# Measurement.net
KiCad netlist of a schematic drawn in Altium Designer
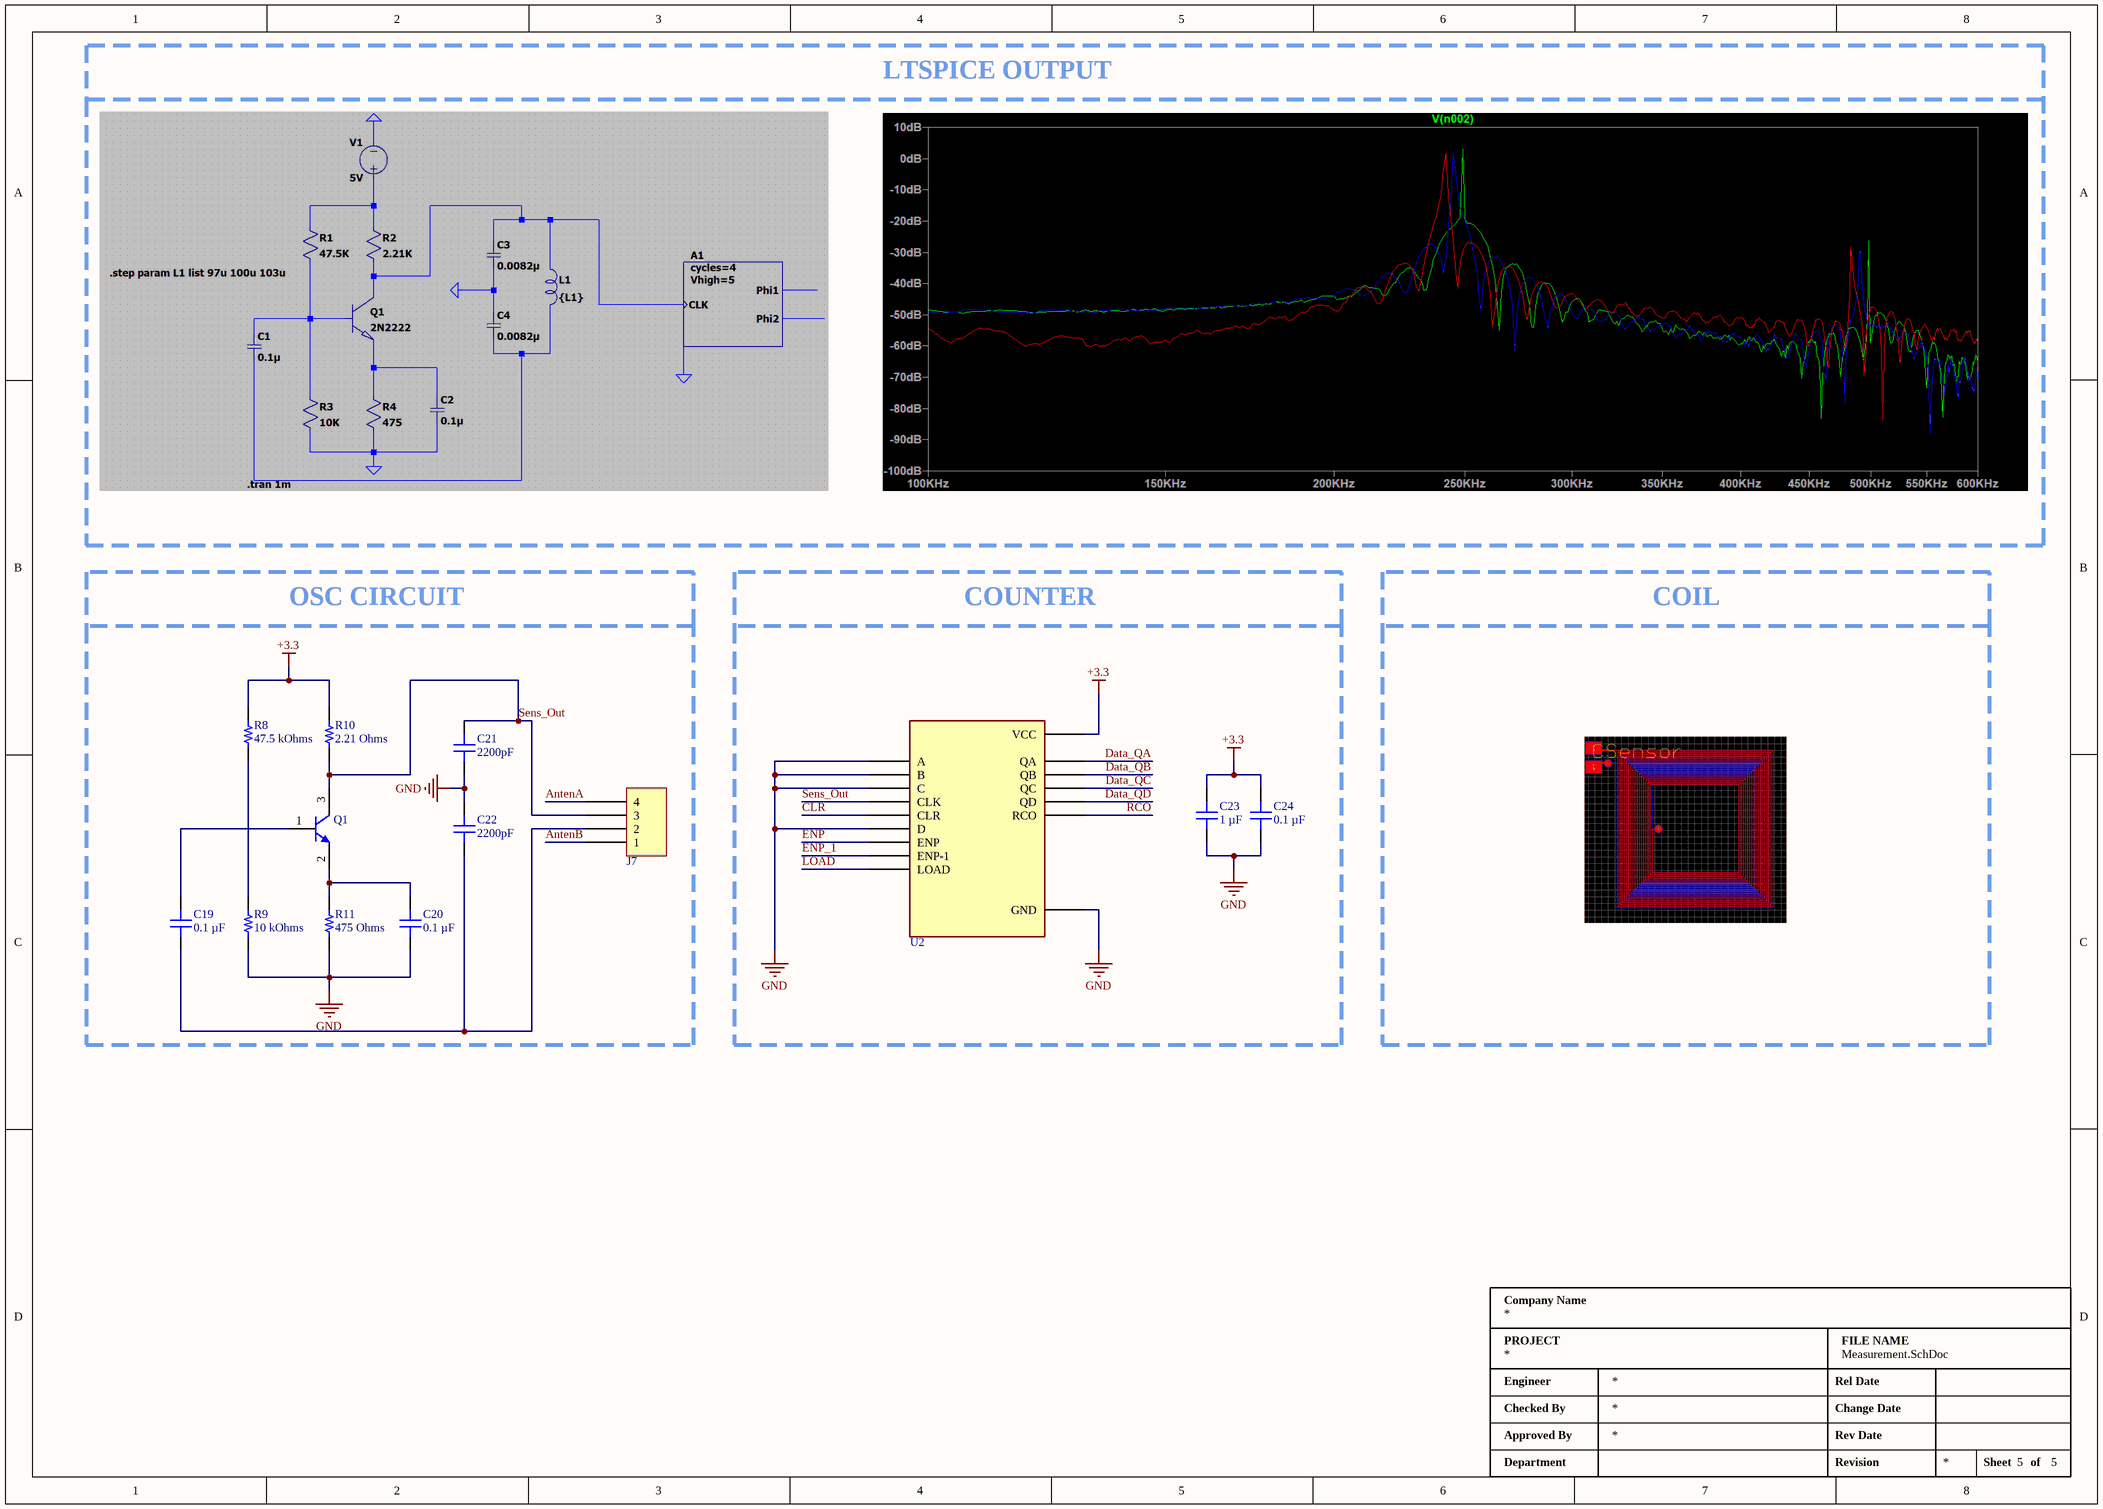
[diagram p0: Measurement.SchDoc]

(export (version "E")
  (design (tool "Eeschema 10.0.6"))
  (components
    (comp (ref "C19")
      (value "0.1 µF")
      (footprint "CAP 0603_1608")
      (description "CAP, Y5V, 0603, 0.1UF, +80/-20%,")
      (fields
        (field (name "PART NUMBER") "CML0603Y5V104ZT50V")
        (field (name "CAPACITANCE") "0.1 µF")
        (field (name "MANUFACTURER") "Stackpole Electronics Inc")
      )
      (libsource (lib "Celestial Altium Library - altium_library") (part "Capacitor"))
    )
    (comp (ref "C20")
      (value "0.1 µF")
      (footprint "CAP 0603_1608")
      (description "CAP, Y5V, 0603, 0.1UF, +80/-20%,")
      (fields
        (field (name "PART NUMBER") "CML0603Y5V104ZT50V")
        (field (name "CAPACITANCE") "0.1 µF")
        (field (name "MANUFACTURER") "Stackpole Electronics Inc")
      )
      (libsource (lib "Celestial Altium Library - altium_library") (part "Capacitor"))
    )
    (comp (ref "C21")
      (value "2200pF")
      (footprint "CAP 0603_1608")
      (description "CAP CER 2200PF 100V X7R 0603")
      (fields
        (field (name "PART NUMBER") "06031C222KAT4A")
        (field (name "CAPACITANCE") "2200pF")
        (field (name "MANUFACTURER") "AVX Corporation")
      )
      (libsource (lib "Celestial Altium Library - altium_library") (part "Capacitor"))
    )
    (comp (ref "C22")
      (value "2200pF")
      (footprint "CAP 0603_1608")
      (description "CAP CER 2200PF 100V X7R 0603")
      (fields
        (field (name "PART NUMBER") "06031C222KAT4A")
        (field (name "CAPACITANCE") "2200pF")
        (field (name "MANUFACTURER") "AVX Corporation")
      )
      (libsource (lib "Celestial Altium Library - altium_library") (part "Capacitor"))
    )
    (comp (ref "C23")
      (value "1 µF")
      (footprint "CAP 0603_1608")
      (description "CAP CER 0603 1UF 16V X7R 20%")
      (fields
        (field (name "PART NUMBER") "C0603X105M4RAC7867")
        (field (name "CAPACITANCE") "1 µF")
        (field (name "MANUFACTURER") "KEMET")
      )
      (libsource (lib "Celestial Altium Library - altium_library") (part "Capacitor"))
    )
    (comp (ref "C24")
      (value "0.1 µF")
      (footprint "CAP 0805_2012")
      (description "CAP CER 0805 0.1UF 100V X7R 5%")
      (fields
        (field (name "PART NUMBER") "C0805C104J1RECAUTO")
        (field (name "CAPACITANCE") "0.1 µF")
        (field (name "MANUFACTURER") "KEMET")
      )
      (libsource (lib "Celestial Altium Library - altium_library") (part "Capacitor"))
    )
    (comp (ref "J7")
      (value "SSW-104-03-T-S")
      (footprint "SAMTEC SSW-104-03-T-S")
      (description "CONN RCPT 4POS 0.1 TIN PCB")
      (fields (field (name "MANUFACTURER") "Samtec Inc."))
      (libsource (lib "Celestial Altium Library - altium_library") (part "4 Pin"))
    )
    (comp (ref "Q1")
      (value "MMBT489LT1G")
      (footprint "ON SEMI SOT-23-3")
      (description "TRANS NPN 30V 1A SOT23")
      (fields (field (name "MANUFACTURER") "ON Semiconductor"))
      (libsource (lib "Celestial Altium Library - altium_library") (part "ON SEMI NPN SOT-23-3"))
    )
    (comp (ref "R8")
      (value "47.5 kOhms")
      (footprint "RES 0603_1608")
      (description "RES SMD 47.5K OHM 0.1% 1/5W 0603")
      (fields
        (field (name "PART NUMBER") "ERJ-PB3B4752V")
        (field (name "MANUFACTURER") "Panasonic Electronic Components")
      )
      (libsource (lib "Celestial Altium Library - altium_library") (part "Resistor"))
    )
    (comp (ref "R9")
      (value "10 kOhms")
      (footprint "RES 0603_1608")
      (description "RES 10K OHM 0.1% 1/16W 0603")
      (fields
        (field (name "PART NUMBER") "RNCS0603BKE10K0")
        (field (name "MANUFACTURER") "Stackpole Electronics Inc")
      )
      (libsource (lib "Celestial Altium Library - altium_library") (part "Resistor"))
    )
    (comp (ref "R10")
      (value "2.21 Ohms")
      (footprint "RES 0603_1608")
      (description "CPF 0603 2R21 0.1% 25PPM 1K RL")
      (fields
        (field (name "PART NUMBER") "CPF0603B2R21E1")
        (field (name "MANUFACTURER") "TE Connectivity Passive Product")
      )
      (libsource (lib "Celestial Altium Library - altium_library") (part "Resistor"))
    )
    (comp (ref "R11")
      (value "475 Ohms")
      (footprint "RES 0603_1608")
      (description "RES SMD 475 OHM 0.5% 1/5W 0603")
      (fields
        (field (name "PART NUMBER") "ERJ-PB3D4750V")
        (field (name "MANUFACTURER") "Panasonic Electronic Components")
      )
      (libsource (lib "Celestial Altium Library - altium_library") (part "Resistor"))
    )
    (comp (ref "U2")
      (value "IC COUNTER 4BIT SYNC BIN 16-SOIC")
      (footprint "SOIC16")
      (fields
        (field (name "MANUFACTURER") "Texas Instruments")
        (field (name "MANUFACTURER PART NUMBER") "SN74HC163DR")
      )
      (libsource (lib "DcDcBuck") (part "SN74HC163D"))
    )
  )
  (nets
    (net (code "1") (name "+3.3") (class "Default")
      (node (ref "C23") (pin "2") (pinfunction "2_2") (pintype "passive"))
      (node (ref "C24") (pin "2") (pinfunction "2_2") (pintype "passive"))
      (node (ref "R10") (pin "2") (pinfunction "2_2") (pintype "passive"))
      (node (ref "R8") (pin "2") (pinfunction "2_2") (pintype "passive"))
      (node (ref "U2") (pin "16") (pinfunction "VCC_16") (pintype "passive"))
    )
    (net (code "2") (name "/AntenA") (class "Default")
      (node (ref "J7") (pin "4") (pinfunction "4_4") (pintype "passive"))
    )
    (net (code "3") (name "/AntenB") (class "Default")
      (node (ref "J7") (pin "1") (pinfunction "1_1") (pintype "passive"))
    )
    (net (code "4") (name "/CLR") (class "Default")
      (node (ref "U2") (pin "1") (pinfunction "CLR_1") (pintype "passive"))
    )
    (net (code "5") (name "/Data_QA") (class "Default")
      (node (ref "U2") (pin "14") (pinfunction "QA_14") (pintype "passive"))
    )
    (net (code "6") (name "/Data_QB") (class "Default")
      (node (ref "U2") (pin "13") (pinfunction "QB_13") (pintype "passive"))
    )
    (net (code "7") (name "/Data_QC") (class "Default")
      (node (ref "U2") (pin "12") (pinfunction "QC_12") (pintype "passive"))
    )
    (net (code "8") (name "/Data_QD") (class "Default")
      (node (ref "U2") (pin "11") (pinfunction "QD_11") (pintype "passive"))
    )
    (net (code "9") (name "/ENP") (class "Default")
      (node (ref "U2") (pin "7") (pinfunction "ENP_7") (pintype "passive"))
    )
    (net (code "10") (name "/ENP_1") (class "Default")
      (node (ref "U2") (pin "10") (pinfunction "ENP-1_10") (pintype "passive"))
    )
    (net (code "11") (name "/LOAD") (class "Default")
      (node (ref "U2") (pin "9") (pinfunction "LOAD_9") (pintype "passive"))
    )
    (net (code "12") (name "/RCO") (class "Default")
      (node (ref "U2") (pin "15") (pinfunction "RCO_15") (pintype "passive"))
    )
    (net (code "13") (name "/Sens_Out") (class "Default")
      (node (ref "C21") (pin "2") (pinfunction "2_2") (pintype "passive"))
      (node (ref "J7") (pin "3") (pinfunction "3_3") (pintype "passive"))
      (node (ref "Q1") (pin "3") (pinfunction "C_3") (pintype "passive"))
      (node (ref "R10") (pin "1") (pinfunction "1_1") (pintype "passive"))
      (node (ref "U2") (pin "2") (pinfunction "CLK_2") (pintype "passive"))
    )
    (net (code "14") (name "GND") (class "Default")
      (node (ref "C20") (pin "1") (pinfunction "1_1") (pintype "passive"))
      (node (ref "C21") (pin "1") (pinfunction "1_1") (pintype "passive"))
      (node (ref "C22") (pin "2") (pinfunction "2_2") (pintype "passive"))
      (node (ref "C23") (pin "1") (pinfunction "1_1") (pintype "passive"))
      (node (ref "C24") (pin "1") (pinfunction "1_1") (pintype "passive"))
      (node (ref "R11") (pin "1") (pinfunction "1_1") (pintype "passive"))
      (node (ref "R9") (pin "1") (pinfunction "1_1") (pintype "passive"))
      (node (ref "U2") (pin "3") (pinfunction "A_3") (pintype "passive"))
      (node (ref "U2") (pin "4") (pinfunction "B_4") (pintype "passive"))
      (node (ref "U2") (pin "5") (pinfunction "C_5") (pintype "passive"))
      (node (ref "U2") (pin "6") (pinfunction "D_6") (pintype "passive"))
      (node (ref "U2") (pin "8") (pinfunction "GND_8") (pintype "passive"))
    )
    (net (code "15") (name "Net-(C19-Pad1)") (class "Default")
      (node (ref "C19") (pin "1") (pinfunction "1_1") (pintype "passive"))
      (node (ref "C22") (pin "1") (pinfunction "1_1") (pintype "passive"))
      (node (ref "J7") (pin "2") (pinfunction "2_2") (pintype "passive"))
    )
    (net (code "16") (name "Net-(Q1-B)") (class "Default")
      (node (ref "C19") (pin "2") (pinfunction "2_2") (pintype "passive"))
      (node (ref "Q1") (pin "1") (pinfunction "B_1") (pintype "passive"))
    )
    (net (code "17") (name "Net-(Q1-E)") (class "Default")
      (node (ref "C20") (pin "2") (pinfunction "2_2") (pintype "passive"))
      (node (ref "Q1") (pin "2") (pinfunction "E_2") (pintype "passive"))
      (node (ref "R11") (pin "2") (pinfunction "2_2") (pintype "passive"))
    )
    (net (code "18") (name "Net-(R8-Pad1)") (class "Default")
      (node (ref "R8") (pin "1") (pinfunction "1_1") (pintype "passive"))
      (node (ref "R9") (pin "2") (pinfunction "2_2") (pintype "passive"))
    )
  )
)
